# Altium_Vacuum_Gauge_V1_1.net
KiCad netlist of a schematic drawn in Altium Designer
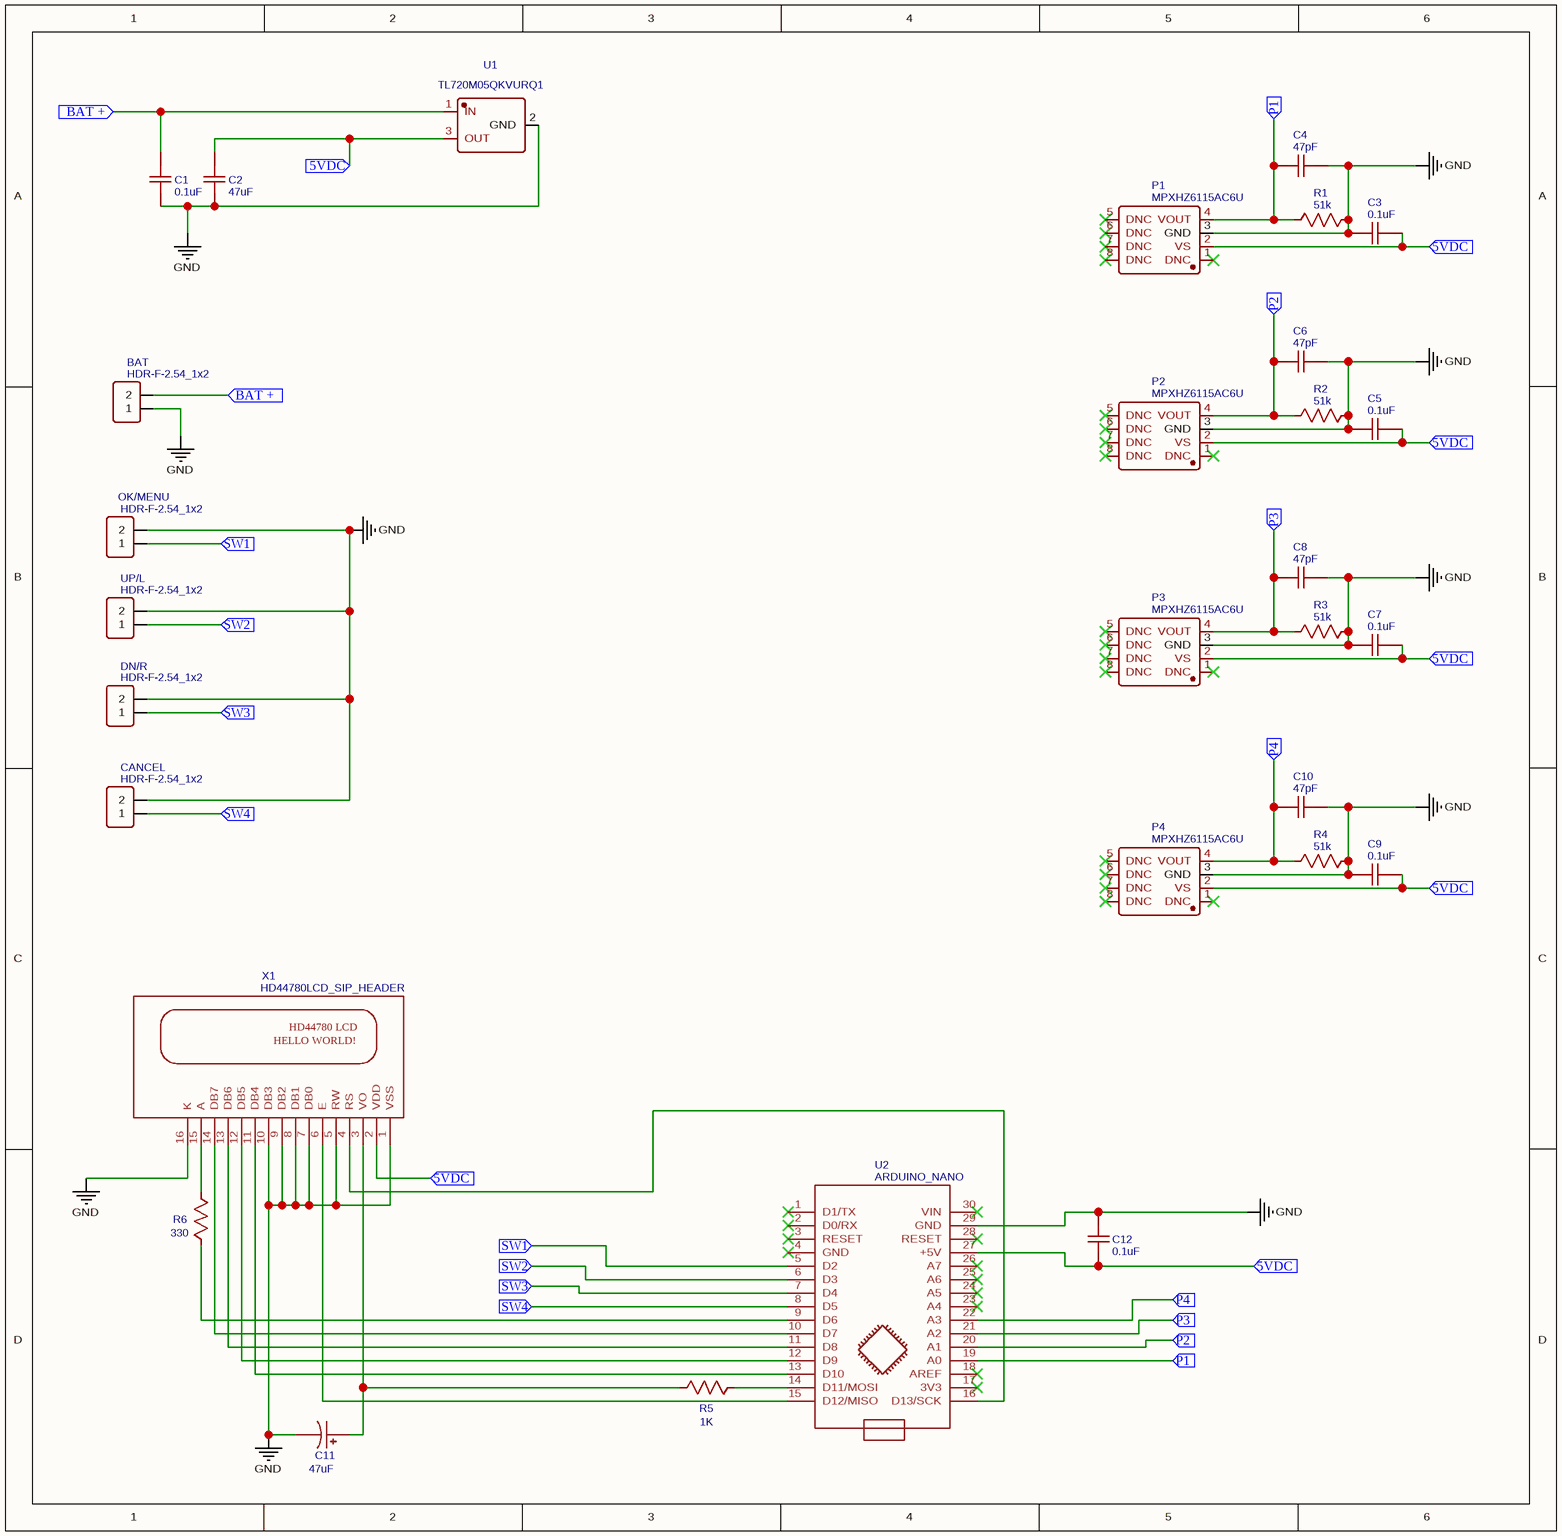
[diagram p0: Altium_Vacuum Gauge V1.1.schdoc]

(export (version "E")
  (design (tool "Eeschema 10.0.6"))
  (components
    (comp (ref "BAT")
      (value "HDR-F-2.54_1x2")
      (fields (field (name "BOM_SUPPLIER PART") "C49661") (field (name "CONTRIBUTOR") "LCEDA_Lib"))
      (libsource (lib "altium-import") (part "root_2_HDR-F-2.54_1x2_"))
    )
    (comp (ref "C1")
      (value "0.1uF")
      (fields (field (name "CONTRIBUTOR") "LCEDA_Lib"))
      (libsource (lib "altium-import") (part "root_1_0.1uF_"))
    )
    (comp (ref "C2")
      (value "47uF")
      (fields (field (name "CONTRIBUTOR") "LCEDA_Lib"))
      (libsource (lib "altium-import") (part "root_1_47uF_"))
    )
    (comp (ref "C3")
      (value "0.1uF")
      (fields (field (name "CONTRIBUTOR") "LCEDA_Lib"))
      (libsource (lib "altium-import") (part "root_2_0.1uF_"))
    )
    (comp (ref "C4")
      (value "47pF")
      (fields (field (name "CONTRIBUTOR") "LCEDA_Lib"))
      (libsource (lib "altium-import") (part "root_2_47pF_"))
    )
    (comp (ref "C5")
      (value "0.1uF")
      (fields (field (name "CONTRIBUTOR") "LCEDA_Lib"))
      (libsource (lib "altium-import") (part "root_2_0.1uF_"))
    )
    (comp (ref "C6")
      (value "47pF")
      (fields (field (name "CONTRIBUTOR") "LCEDA_Lib"))
      (libsource (lib "altium-import") (part "root_2_47pF_"))
    )
    (comp (ref "C7")
      (value "0.1uF")
      (fields (field (name "CONTRIBUTOR") "LCEDA_Lib"))
      (libsource (lib "altium-import") (part "root_2_0.1uF_"))
    )
    (comp (ref "C8")
      (value "47pF")
      (fields (field (name "CONTRIBUTOR") "LCEDA_Lib"))
      (libsource (lib "altium-import") (part "root_2_47pF_"))
    )
    (comp (ref "C9")
      (value "0.1uF")
      (fields (field (name "CONTRIBUTOR") "LCEDA_Lib"))
      (libsource (lib "altium-import") (part "root_2_0.1uF_"))
    )
    (comp (ref "C10")
      (value "47pF")
      (fields (field (name "CONTRIBUTOR") "LCEDA_Lib"))
      (libsource (lib "altium-import") (part "root_2_47pF_"))
    )
    (comp (ref "C11")
      (value "47uF")
      (fields (field (name "CONTRIBUTOR") "LCEDA_Lib"))
      (libsource (lib "altium-import") (part "root_2_47uF_"))
    )
    (comp (ref "C12")
      (value "0.1uF")
      (fields (field (name "CONTRIBUTOR") "LCEDA_Lib"))
      (libsource (lib "altium-import") (part "root_3_0.1uF_"))
    )
    (comp (ref "CANCEL")
      (value "HDR-F-2.54_1x2")
      (fields (field (name "BOM_SUPPLIER PART") "C49661") (field (name "CONTRIBUTOR") "LCEDA_Lib"))
      (libsource (lib "altium-import") (part "root_2_HDR-F-2.54_1x2_"))
    )
    (comp (ref "DN/R")
      (value "HDR-F-2.54_1x2")
      (fields (field (name "BOM_SUPPLIER PART") "C49661") (field (name "CONTRIBUTOR") "LCEDA_Lib"))
      (libsource (lib "altium-import") (part "root_2_HDR-F-2.54_1x2_"))
    )
    (comp (ref "OK/MENU")
      (value "HDR-F-2.54_1x2")
      (fields (field (name "BOM_SUPPLIER PART") "C49661") (field (name "CONTRIBUTOR") "LCEDA_Lib"))
      (libsource (lib "altium-import") (part "root_2_HDR-F-2.54_1x2_"))
    )
    (comp (ref "P1")
      (value "MPXHZ6115AC6U")
      (fields
        (field (name "BOM_SUPPLIER PART") "C511770")
        (field (name "BOM_MANUFACTURER PART") "MPXHZ6400AC6T1")
        (field (name "CONTRIBUTOR") "LCSC")
      )
      (libsource (lib "altium-import") (part "root_0_MPXHZ6115AC6U_"))
    )
    (comp (ref "P2")
      (value "MPXHZ6115AC6U")
      (fields
        (field (name "BOM_SUPPLIER PART") "C511770")
        (field (name "BOM_MANUFACTURER PART") "MPXHZ6400AC6T1")
        (field (name "CONTRIBUTOR") "LCSC")
      )
      (libsource (lib "altium-import") (part "root_0_MPXHZ6115AC6U_"))
    )
    (comp (ref "P3")
      (value "MPXHZ6115AC6U")
      (fields
        (field (name "BOM_SUPPLIER PART") "C511770")
        (field (name "BOM_MANUFACTURER PART") "MPXHZ6400AC6T1")
        (field (name "CONTRIBUTOR") "LCSC")
      )
      (libsource (lib "altium-import") (part "root_0_MPXHZ6115AC6U_"))
    )
    (comp (ref "P4")
      (value "MPXHZ6115AC6U")
      (fields
        (field (name "BOM_SUPPLIER PART") "C511770")
        (field (name "BOM_MANUFACTURER PART") "MPXHZ6400AC6T1")
        (field (name "CONTRIBUTOR") "LCSC")
      )
      (libsource (lib "altium-import") (part "root_0_MPXHZ6115AC6U_"))
    )
    (comp (ref "R1")
      (value "51k")
      (fields (field (name "CONTRIBUTOR") "LCEDA_Lib"))
      (libsource (lib "altium-import") (part "root_0_51k_"))
    )
    (comp (ref "R2")
      (value "51k")
      (fields (field (name "CONTRIBUTOR") "LCEDA_Lib"))
      (libsource (lib "altium-import") (part "root_0_51k_"))
    )
    (comp (ref "R3")
      (value "51k")
      (fields (field (name "CONTRIBUTOR") "LCEDA_Lib"))
      (libsource (lib "altium-import") (part "root_0_51k_"))
    )
    (comp (ref "R4")
      (value "51k")
      (fields (field (name "CONTRIBUTOR") "LCEDA_Lib"))
      (libsource (lib "altium-import") (part "root_0_51k_"))
    )
    (comp (ref "R5")
      (value "1K")
      (fields (field (name "CONTRIBUTOR") "LCEDA_Lib"))
      (libsource (lib "altium-import") (part "root_0_1K_"))
    )
    (comp (ref "R6")
      (value "330")
      (fields (field (name "CONTRIBUTOR") "LCEDA_Lib"))
      (libsource (lib "altium-import") (part "root_3_330_"))
    )
    (comp (ref "U1")
      (value "TL720M05QKVURQ1")
      (fields (field (name "BOM_SUPPLIER PART") "C486028") (field (name "CONTRIBUTOR") "LCSC"))
      (libsource (lib "altium-import") (part "root_0_TL720M05QKVURQ1_"))
    )
    (comp (ref "U2") (value "ARDUINO_NANO") (libsource (lib "altium-import") (part "root_0_ARDUINO_NANO_")))
    (comp (ref "UP/L")
      (value "HDR-F-2.54_1x2")
      (fields (field (name "BOM_SUPPLIER PART") "C49661") (field (name "CONTRIBUTOR") "LCEDA_Lib"))
      (libsource (lib "altium-import") (part "root_2_HDR-F-2.54_1x2_"))
    )
    (comp (ref "X1")
      (value "HD44780LCD_SIP_HEADER")
      (fields (field (name "CONTRIBUTOR") "krmoyle76"))
      (libsource (lib "altium-import") (part "root_2_HD44780LCD_SIP_HEADER_"))
    )
  )
  (nets
    (net (code "1") (name "/5VDC") (class "Default")
      (node (ref "C12") (pin "2") (pinfunction "2_2") (pintype "passive"))
      (node (ref "C2") (pin "2") (pinfunction "2_2") (pintype "passive"))
      (node (ref "C3") (pin "1") (pinfunction "1_1") (pintype "passive"))
      (node (ref "C5") (pin "1") (pinfunction "1_1") (pintype "passive"))
      (node (ref "C7") (pin "1") (pinfunction "1_1") (pintype "passive"))
      (node (ref "C9") (pin "1") (pinfunction "1_1") (pintype "passive"))
      (node (ref "P1") (pin "2") (pinfunction "VS_2") (pintype "passive"))
      (node (ref "P2") (pin "2") (pinfunction "VS_2") (pintype "passive"))
      (node (ref "P3") (pin "2") (pinfunction "VS_2") (pintype "passive"))
      (node (ref "P4") (pin "2") (pinfunction "VS_2") (pintype "passive"))
      (node (ref "U1") (pin "3") (pinfunction "OUT_3") (pintype "passive"))
      (node (ref "U2") (pin "27") (pinfunction "+5V_27") (pintype "passive"))
      (node (ref "X1") (pin "2") (pinfunction "VDD_2") (pintype "passive"))
    )
    (net (code "2") (name "/BAT +") (class "Default")
      (node (ref "BAT") (pin "2") (pinfunction "2_2") (pintype "passive"))
      (node (ref "C1") (pin "2") (pinfunction "2_2") (pintype "passive"))
      (node (ref "U1") (pin "1") (pinfunction "IN_1") (pintype "passive"))
    )
    (net (code "3") (name "/P1") (class "Default")
      (node (ref "C4") (pin "2") (pinfunction "2_2") (pintype "passive"))
      (node (ref "P1") (pin "4") (pinfunction "VOUT_4") (pintype "passive"))
      (node (ref "R1") (pin "1") (pinfunction "1_1") (pintype "passive"))
      (node (ref "U2") (pin "19") (pinfunction "A0_19") (pintype "passive"))
    )
    (net (code "4") (name "/P2") (class "Default")
      (node (ref "C6") (pin "2") (pinfunction "2_2") (pintype "passive"))
      (node (ref "P2") (pin "4") (pinfunction "VOUT_4") (pintype "passive"))
      (node (ref "R2") (pin "1") (pinfunction "1_1") (pintype "passive"))
      (node (ref "U2") (pin "20") (pinfunction "A1_20") (pintype "passive"))
    )
    (net (code "5") (name "/P3") (class "Default")
      (node (ref "C8") (pin "2") (pinfunction "2_2") (pintype "passive"))
      (node (ref "P3") (pin "4") (pinfunction "VOUT_4") (pintype "passive"))
      (node (ref "R3") (pin "1") (pinfunction "1_1") (pintype "passive"))
      (node (ref "U2") (pin "21") (pinfunction "A2_21") (pintype "passive"))
    )
    (net (code "6") (name "/P4") (class "Default")
      (node (ref "C10") (pin "2") (pinfunction "2_2") (pintype "passive"))
      (node (ref "P4") (pin "4") (pinfunction "VOUT_4") (pintype "passive"))
      (node (ref "R4") (pin "1") (pinfunction "1_1") (pintype "passive"))
      (node (ref "U2") (pin "22") (pinfunction "A3_22") (pintype "passive"))
    )
    (net (code "7") (name "/SW1") (class "Default")
      (node (ref "OK/MENU") (pin "1") (pinfunction "1_1") (pintype "passive"))
      (node (ref "U2") (pin "5") (pinfunction "D2_5") (pintype "passive"))
    )
    (net (code "8") (name "/SW2") (class "Default")
      (node (ref "U2") (pin "6") (pinfunction "D3_6") (pintype "passive"))
      (node (ref "UP/L") (pin "1") (pinfunction "1_1") (pintype "passive"))
    )
    (net (code "9") (name "/SW3") (class "Default")
      (node (ref "DN/R") (pin "1") (pinfunction "1_1") (pintype "passive"))
      (node (ref "U2") (pin "7") (pinfunction "D4_7") (pintype "passive"))
    )
    (net (code "10") (name "/SW4") (class "Default")
      (node (ref "CANCEL") (pin "1") (pinfunction "1_1") (pintype "passive"))
      (node (ref "U2") (pin "8") (pinfunction "D5_8") (pintype "passive"))
    )
    (net (code "11") (name "GND") (class "Default")
      (node (ref "BAT") (pin "1") (pinfunction "1_1") (pintype "passive"))
      (node (ref "C1") (pin "1") (pinfunction "1_1") (pintype "passive"))
      (node (ref "C10") (pin "1") (pinfunction "1_1") (pintype "passive"))
      (node (ref "C11") (pin "2") (pinfunction "2_2") (pintype "passive"))
      (node (ref "C12") (pin "1") (pinfunction "1_1") (pintype "passive"))
      (node (ref "C2") (pin "1") (pinfunction "1_1") (pintype "passive"))
      (node (ref "C3") (pin "2") (pinfunction "2_2") (pintype "passive"))
      (node (ref "C4") (pin "1") (pinfunction "1_1") (pintype "passive"))
      (node (ref "C5") (pin "2") (pinfunction "2_2") (pintype "passive"))
      (node (ref "C6") (pin "1") (pinfunction "1_1") (pintype "passive"))
      (node (ref "C7") (pin "2") (pinfunction "2_2") (pintype "passive"))
      (node (ref "C8") (pin "1") (pinfunction "1_1") (pintype "passive"))
      (node (ref "C9") (pin "2") (pinfunction "2_2") (pintype "passive"))
      (node (ref "CANCEL") (pin "2") (pinfunction "2_2") (pintype "passive"))
      (node (ref "DN/R") (pin "2") (pinfunction "2_2") (pintype "passive"))
      (node (ref "OK/MENU") (pin "2") (pinfunction "2_2") (pintype "passive"))
      (node (ref "P1") (pin "3") (pinfunction "GND_3") (pintype "passive"))
      (node (ref "P2") (pin "3") (pinfunction "GND_3") (pintype "passive"))
      (node (ref "P3") (pin "3") (pinfunction "GND_3") (pintype "passive"))
      (node (ref "P4") (pin "3") (pinfunction "GND_3") (pintype "passive"))
      (node (ref "R1") (pin "2") (pinfunction "2_2") (pintype "passive"))
      (node (ref "R2") (pin "2") (pinfunction "2_2") (pintype "passive"))
      (node (ref "R3") (pin "2") (pinfunction "2_2") (pintype "passive"))
      (node (ref "R4") (pin "2") (pinfunction "2_2") (pintype "passive"))
      (node (ref "U1") (pin "2") (pinfunction "GND_2") (pintype "passive"))
      (node (ref "U2") (pin "29") (pinfunction "GND_29") (pintype "passive"))
      (node (ref "UP/L") (pin "2") (pinfunction "2_2") (pintype "passive"))
      (node (ref "X1") (pin "1") (pinfunction "VSS_1") (pintype "passive"))
      (node (ref "X1") (pin "10") (pinfunction "DB3_10") (pintype "passive"))
      (node (ref "X1") (pin "16") (pinfunction "K_16") (pintype "passive"))
      (node (ref "X1") (pin "5") (pinfunction "RW_5") (pintype "passive"))
      (node (ref "X1") (pin "7") (pinfunction "DB0_7") (pintype "passive"))
      (node (ref "X1") (pin "8") (pinfunction "DB1_8") (pintype "passive"))
      (node (ref "X1") (pin "9") (pinfunction "DB2_9") (pintype "passive"))
    )
    (net (code "12") (name "Net-(U2-D6)") (class "Default")
      (node (ref "R6") (pin "2") (pinfunction "2_2") (pintype "passive"))
      (node (ref "U2") (pin "9") (pinfunction "D6_9") (pintype "passive"))
    )
    (net (code "13") (name "Net-(U2-D7)") (class "Default")
      (node (ref "U2") (pin "10") (pinfunction "D7_10") (pintype "passive"))
      (node (ref "X1") (pin "14") (pinfunction "DB7_14") (pintype "passive"))
    )
    (net (code "14") (name "Net-(U2-D8)") (class "Default")
      (node (ref "U2") (pin "11") (pinfunction "D8_11") (pintype "passive"))
      (node (ref "X1") (pin "13") (pinfunction "DB6_13") (pintype "passive"))
    )
    (net (code "15") (name "Net-(U2-D9)") (class "Default")
      (node (ref "U2") (pin "12") (pinfunction "D9_12") (pintype "passive"))
      (node (ref "X1") (pin "12") (pinfunction "DB5_12") (pintype "passive"))
    )
    (net (code "16") (name "Net-(U2-D10)") (class "Default")
      (node (ref "U2") (pin "13") (pinfunction "D10_13") (pintype "passive"))
      (node (ref "X1") (pin "11") (pinfunction "DB4_11") (pintype "passive"))
    )
    (net (code "17") (name "Net-(U2-D11{slash}MOSI)") (class "Default")
      (node (ref "R5") (pin "2") (pinfunction "2_2") (pintype "passive"))
      (node (ref "U2") (pin "14") (pinfunction "D11/MOSI_14") (pintype "passive"))
    )
    (net (code "18") (name "Net-(U2-D12{slash}MISO)") (class "Default")
      (node (ref "U2") (pin "15") (pinfunction "D12/MISO_15") (pintype "passive"))
      (node (ref "X1") (pin "6") (pinfunction "E_6") (pintype "passive"))
    )
    (net (code "19") (name "Net-(U2-D13{slash}SCK)") (class "Default")
      (node (ref "U2") (pin "16") (pinfunction "D13/SCK_16") (pintype "passive"))
      (node (ref "X1") (pin "4") (pinfunction "RS_4") (pintype "passive"))
    )
    (net (code "20") (name "Net-(X1-A)") (class "Default")
      (node (ref "R6") (pin "1") (pinfunction "1_1") (pintype "passive"))
      (node (ref "X1") (pin "15") (pinfunction "A_15") (pintype "passive"))
    )
    (net (code "21") (name "Net-(X1-VO)") (class "Default")
      (node (ref "C11") (pin "1") (pinfunction "1_1") (pintype "passive"))
      (node (ref "R5") (pin "1") (pinfunction "1_1") (pintype "passive"))
      (node (ref "X1") (pin "3") (pinfunction "VO_3") (pintype "passive"))
    )
    (net (code "22") (name "unconnected-(P1-DNC-Pad1)") (class "Default")
      (node (ref "P1") (pin "1") (pinfunction "DNC_1") (pintype "passive+no_connect"))
    )
    (net (code "23") (name "unconnected-(P1-DNC-Pad5)") (class "Default")
      (node (ref "P1") (pin "5") (pinfunction "DNC_5") (pintype "passive+no_connect"))
    )
    (net (code "24") (name "unconnected-(P1-DNC-Pad6)") (class "Default")
      (node (ref "P1") (pin "6") (pinfunction "DNC_6") (pintype "passive+no_connect"))
    )
    (net (code "25") (name "unconnected-(P1-DNC-Pad7)") (class "Default")
      (node (ref "P1") (pin "7") (pinfunction "DNC_7") (pintype "passive+no_connect"))
    )
    (net (code "26") (name "unconnected-(P1-DNC-Pad8)") (class "Default")
      (node (ref "P1") (pin "8") (pinfunction "DNC_8") (pintype "passive+no_connect"))
    )
    (net (code "27") (name "unconnected-(P2-DNC-Pad1)") (class "Default")
      (node (ref "P2") (pin "1") (pinfunction "DNC_1") (pintype "passive+no_connect"))
    )
    (net (code "28") (name "unconnected-(P2-DNC-Pad5)") (class "Default")
      (node (ref "P2") (pin "5") (pinfunction "DNC_5") (pintype "passive+no_connect"))
    )
    (net (code "29") (name "unconnected-(P2-DNC-Pad6)") (class "Default")
      (node (ref "P2") (pin "6") (pinfunction "DNC_6") (pintype "passive+no_connect"))
    )
    (net (code "30") (name "unconnected-(P2-DNC-Pad7)") (class "Default")
      (node (ref "P2") (pin "7") (pinfunction "DNC_7") (pintype "passive+no_connect"))
    )
    (net (code "31") (name "unconnected-(P2-DNC-Pad8)") (class "Default")
      (node (ref "P2") (pin "8") (pinfunction "DNC_8") (pintype "passive+no_connect"))
    )
    (net (code "32") (name "unconnected-(P3-DNC-Pad1)") (class "Default")
      (node (ref "P3") (pin "1") (pinfunction "DNC_1") (pintype "passive+no_connect"))
    )
    (net (code "33") (name "unconnected-(P3-DNC-Pad5)") (class "Default")
      (node (ref "P3") (pin "5") (pinfunction "DNC_5") (pintype "passive+no_connect"))
    )
    (net (code "34") (name "unconnected-(P3-DNC-Pad6)") (class "Default")
      (node (ref "P3") (pin "6") (pinfunction "DNC_6") (pintype "passive+no_connect"))
    )
    (net (code "35") (name "unconnected-(P3-DNC-Pad7)") (class "Default")
      (node (ref "P3") (pin "7") (pinfunction "DNC_7") (pintype "passive+no_connect"))
    )
    (net (code "36") (name "unconnected-(P3-DNC-Pad8)") (class "Default")
      (node (ref "P3") (pin "8") (pinfunction "DNC_8") (pintype "passive+no_connect"))
    )
    (net (code "37") (name "unconnected-(P4-DNC-Pad1)") (class "Default")
      (node (ref "P4") (pin "1") (pinfunction "DNC_1") (pintype "passive+no_connect"))
    )
    (net (code "38") (name "unconnected-(P4-DNC-Pad5)") (class "Default")
      (node (ref "P4") (pin "5") (pinfunction "DNC_5") (pintype "passive+no_connect"))
    )
    (net (code "39") (name "unconnected-(P4-DNC-Pad6)") (class "Default")
      (node (ref "P4") (pin "6") (pinfunction "DNC_6") (pintype "passive+no_connect"))
    )
    (net (code "40") (name "unconnected-(P4-DNC-Pad7)") (class "Default")
      (node (ref "P4") (pin "7") (pinfunction "DNC_7") (pintype "passive+no_connect"))
    )
    (net (code "41") (name "unconnected-(P4-DNC-Pad8)") (class "Default")
      (node (ref "P4") (pin "8") (pinfunction "DNC_8") (pintype "passive+no_connect"))
    )
    (net (code "42") (name "unconnected-(U2-3V3-Pad17)") (class "Default")
      (node (ref "U2") (pin "17") (pinfunction "3V3_17") (pintype "passive+no_connect"))
    )
    (net (code "43") (name "unconnected-(U2-A4-Pad23)") (class "Default")
      (node (ref "U2") (pin "23") (pinfunction "A4_23") (pintype "passive+no_connect"))
    )
    (net (code "44") (name "unconnected-(U2-A5-Pad24)") (class "Default")
      (node (ref "U2") (pin "24") (pinfunction "A5_24") (pintype "passive+no_connect"))
    )
    (net (code "45") (name "unconnected-(U2-A6-Pad25)") (class "Default")
      (node (ref "U2") (pin "25") (pinfunction "A6_25") (pintype "passive+no_connect"))
    )
    (net (code "46") (name "unconnected-(U2-A7-Pad26)") (class "Default")
      (node (ref "U2") (pin "26") (pinfunction "A7_26") (pintype "passive+no_connect"))
    )
    (net (code "47") (name "unconnected-(U2-AREF-Pad18)") (class "Default")
      (node (ref "U2") (pin "18") (pinfunction "AREF_18") (pintype "passive+no_connect"))
    )
    (net (code "48") (name "unconnected-(U2-D0{slash}RX-Pad2)") (class "Default")
      (node (ref "U2") (pin "2") (pinfunction "D0/RX_2") (pintype "passive+no_connect"))
    )
    (net (code "49") (name "unconnected-(U2-D1{slash}TX-Pad1)") (class "Default")
      (node (ref "U2") (pin "1") (pinfunction "D1/TX_1") (pintype "passive+no_connect"))
    )
    (net (code "50") (name "unconnected-(U2-GND-Pad4)") (class "Default")
      (node (ref "U2") (pin "4") (pinfunction "GND_4") (pintype "passive+no_connect"))
    )
    (net (code "51") (name "unconnected-(U2-RESET-Pad3)") (class "Default")
      (node (ref "U2") (pin "3") (pinfunction "RESET_3") (pintype "passive+no_connect"))
    )
    (net (code "52") (name "unconnected-(U2-RESET-Pad28)") (class "Default")
      (node (ref "U2") (pin "28") (pinfunction "RESET_28") (pintype "passive+no_connect"))
    )
    (net (code "53") (name "unconnected-(U2-VIN-Pad30)") (class "Default")
      (node (ref "U2") (pin "30") (pinfunction "VIN_30") (pintype "passive+no_connect"))
    )
  )
)
